# Generator_1kHz.net
KiCad netlist of a schematic drawn in Altium Designer
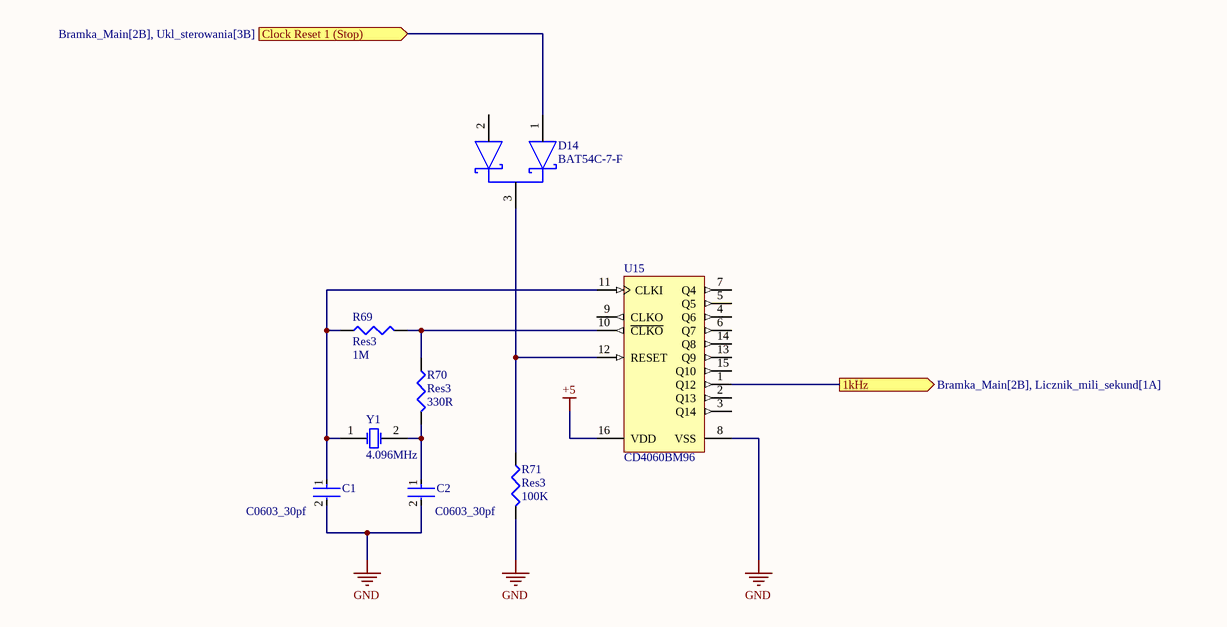
[diagram p0: Generator_1kHz.SchDoc]

(export (version "E")
  (design (tool "Eeschema 10.0.6"))
  (components
    (comp (ref "C1")
      (value "C0603_30pf")
      (footprint "FP-C0603C-CF-MFG")
      (description "CAP CER 30PF 50V 5% NP0 0603")
      (fields
        (field (name "MANUFACTURER PART NUMBER") "C0603C300J5GACTU")
        (field (name "MANUFACTURER") "KEMET")
      )
      (libsource (lib "Altium Content Vault") (part "b4654b650e69147ec39a6b967a45e02"))
    )
    (comp (ref "C2")
      (value "C0603_30pf")
      (footprint "FP-C0603C-CF-MFG")
      (description "CAP CER 30PF 50V 5% NP0 0603")
      (fields
        (field (name "MANUFACTURER PART NUMBER") "C0603C300J5GACTU")
        (field (name "MANUFACTURER") "KEMET")
      )
      (libsource (lib "Altium Content Vault") (part "b4654b650e69147ec39a6b967a45e02"))
    )
    (comp (ref "D14")
      (value "BAT54C-7-F")
      (footprint "FP-SOT23-IPC_B")
      (description "DIODE ARRAY SCHOTTKY 30V SOT23-3")
      (libsource (lib "Altium Content Vault") (part "3eac2aa0c1ac86323ecc23460aa29c6"))
    )
    (comp (ref "R69")
      (value "Res3")
      (footprint "J1-0603")
      (description "Resistor")
      (fields (field (name "ALTIUM_VALUE") "1M") (field (name "PUBLISHER") "Altium Limited"))
      (libsource (lib "Miscellaneous Devices") (part "Res3"))
    )
    (comp (ref "R70")
      (value "Res3")
      (footprint "J1-0603")
      (description "Resistor")
      (fields (field (name "ALTIUM_VALUE") "330R") (field (name "PUBLISHER") "Altium Limited"))
      (libsource (lib "Miscellaneous Devices") (part "Res3"))
    )
    (comp (ref "R71")
      (value "Res3")
      (footprint "J1-0603")
      (description "Resistor")
      (fields (field (name "ALTIUM_VALUE") "100K") (field (name "PUBLISHER") "Altium Limited"))
      (libsource (lib "Miscellaneous Devices") (part "Res3"))
    )
    (comp (ref "U15")
      (value "CD4060BM96")
      (footprint "D0016A_L")
      (fields (field (name "MANUFACTURER") "Texas Instruments"))
      (libsource (lib "Altium Content Vault") (part "TI-CD4060B-16"))
    )
    (comp (ref "Y1")
      (value "4.096MHz")
      (footprint "R38")
      (description "Crystal Oscillator")
      (fields (field (name "PUBLISHER") "Altium Limited"))
      (libsource (lib "Miscellaneous Devices") (part "XTAL"))
    )
  )
  (nets
    (net (code "1") (name "+5") (class "Default")
      (node (ref "U15") (pin "16") (pinfunction "VDD_16") (pintype "power_in"))
    )
    (net (code "2") (name "/1kHz") (class "Default")
      (node (ref "U15") (pin "1") (pinfunction "Q12_1") (pintype "output"))
    )
    (net (code "3") (name "/Clock Reset 1 (Stop)") (class "Default")
      (node (ref "D14") (pin "1") (pinfunction "1_ANODE_1") (pintype "passive"))
    )
    (net (code "4") (name "GND") (class "Default")
      (node (ref "C1") (pin "2") (pinfunction "2_2") (pintype "passive"))
      (node (ref "C2") (pin "2") (pinfunction "2_2") (pintype "passive"))
      (node (ref "R71") (pin "2") (pinfunction "2_2") (pintype "passive"))
      (node (ref "U15") (pin "8") (pinfunction "VSS_8") (pintype "power_in"))
    )
    (net (code "5") (name "Net-(D14-COMMON_CATHODE)") (class "Default")
      (node (ref "D14") (pin "3") (pinfunction "COMMON_CATHODE_3") (pintype "passive"))
      (node (ref "R71") (pin "1") (pinfunction "1_1") (pintype "passive"))
      (node (ref "U15") (pin "12") (pinfunction "RESET_12") (pintype "input"))
    )
    (net (code "6") (name "Net-(U15-CLKI)") (class "Default")
      (node (ref "C1") (pin "1") (pinfunction "1_1") (pintype "passive"))
      (node (ref "R69") (pin "1") (pinfunction "1_1") (pintype "passive"))
      (node (ref "U15") (pin "11") (pinfunction "CLKI_11") (pintype "input"))
      (node (ref "Y1") (pin "1") (pinfunction "OSC1_1") (pintype "passive"))
    )
    (net (code "7") (name "Net-(U15-~{CLKO})") (class "Default")
      (node (ref "R69") (pin "2") (pinfunction "2_2") (pintype "passive"))
      (node (ref "R70") (pin "1") (pinfunction "1_1") (pintype "passive"))
      (node (ref "U15") (pin "10") (pinfunction "~{CLKO}_10") (pintype "output"))
    )
    (net (code "8") (name "Net-(Y1-OSC2)") (class "Default")
      (node (ref "C2") (pin "1") (pinfunction "1_1") (pintype "passive"))
      (node (ref "R70") (pin "2") (pinfunction "2_2") (pintype "passive"))
      (node (ref "Y1") (pin "2") (pinfunction "OSC2_2") (pintype "passive"))
    )
    (net (code "9") (name "unconnected-(D14-2_ANODE-Pad2)") (class "Default")
      (node (ref "D14") (pin "2") (pinfunction "2_ANODE_2") (pintype "passive"))
    )
    (net (code "10") (name "unconnected-(U15-CLKO-Pad9)") (class "Default")
      (node (ref "U15") (pin "9") (pinfunction "CLKO_9") (pintype "output"))
    )
    (net (code "11") (name "unconnected-(U15-Q4-Pad7)") (class "Default")
      (node (ref "U15") (pin "7") (pinfunction "Q4_7") (pintype "output"))
    )
    (net (code "12") (name "unconnected-(U15-Q5-Pad5)") (class "Default")
      (node (ref "U15") (pin "5") (pinfunction "Q5_5") (pintype "output"))
    )
    (net (code "13") (name "unconnected-(U15-Q6-Pad4)") (class "Default")
      (node (ref "U15") (pin "4") (pinfunction "Q6_4") (pintype "output"))
    )
    (net (code "14") (name "unconnected-(U15-Q7-Pad6)") (class "Default")
      (node (ref "U15") (pin "6") (pinfunction "Q7_6") (pintype "output"))
    )
    (net (code "15") (name "unconnected-(U15-Q8-Pad14)") (class "Default")
      (node (ref "U15") (pin "14") (pinfunction "Q8_14") (pintype "output"))
    )
    (net (code "16") (name "unconnected-(U15-Q9-Pad13)") (class "Default")
      (node (ref "U15") (pin "13") (pinfunction "Q9_13") (pintype "output"))
    )
    (net (code "17") (name "unconnected-(U15-Q10-Pad15)") (class "Default")
      (node (ref "U15") (pin "15") (pinfunction "Q10_15") (pintype "output"))
    )
    (net (code "18") (name "unconnected-(U15-Q13-Pad2)") (class "Default")
      (node (ref "U15") (pin "2") (pinfunction "Q13_2") (pintype "output"))
    )
    (net (code "19") (name "unconnected-(U15-Q14-Pad3)") (class "Default")
      (node (ref "U15") (pin "3") (pinfunction "Q14_3") (pintype "output"))
    )
  )
)
